# SCH-00005-6.net
KiCad netlist of a schematic drawn in Altium Designer
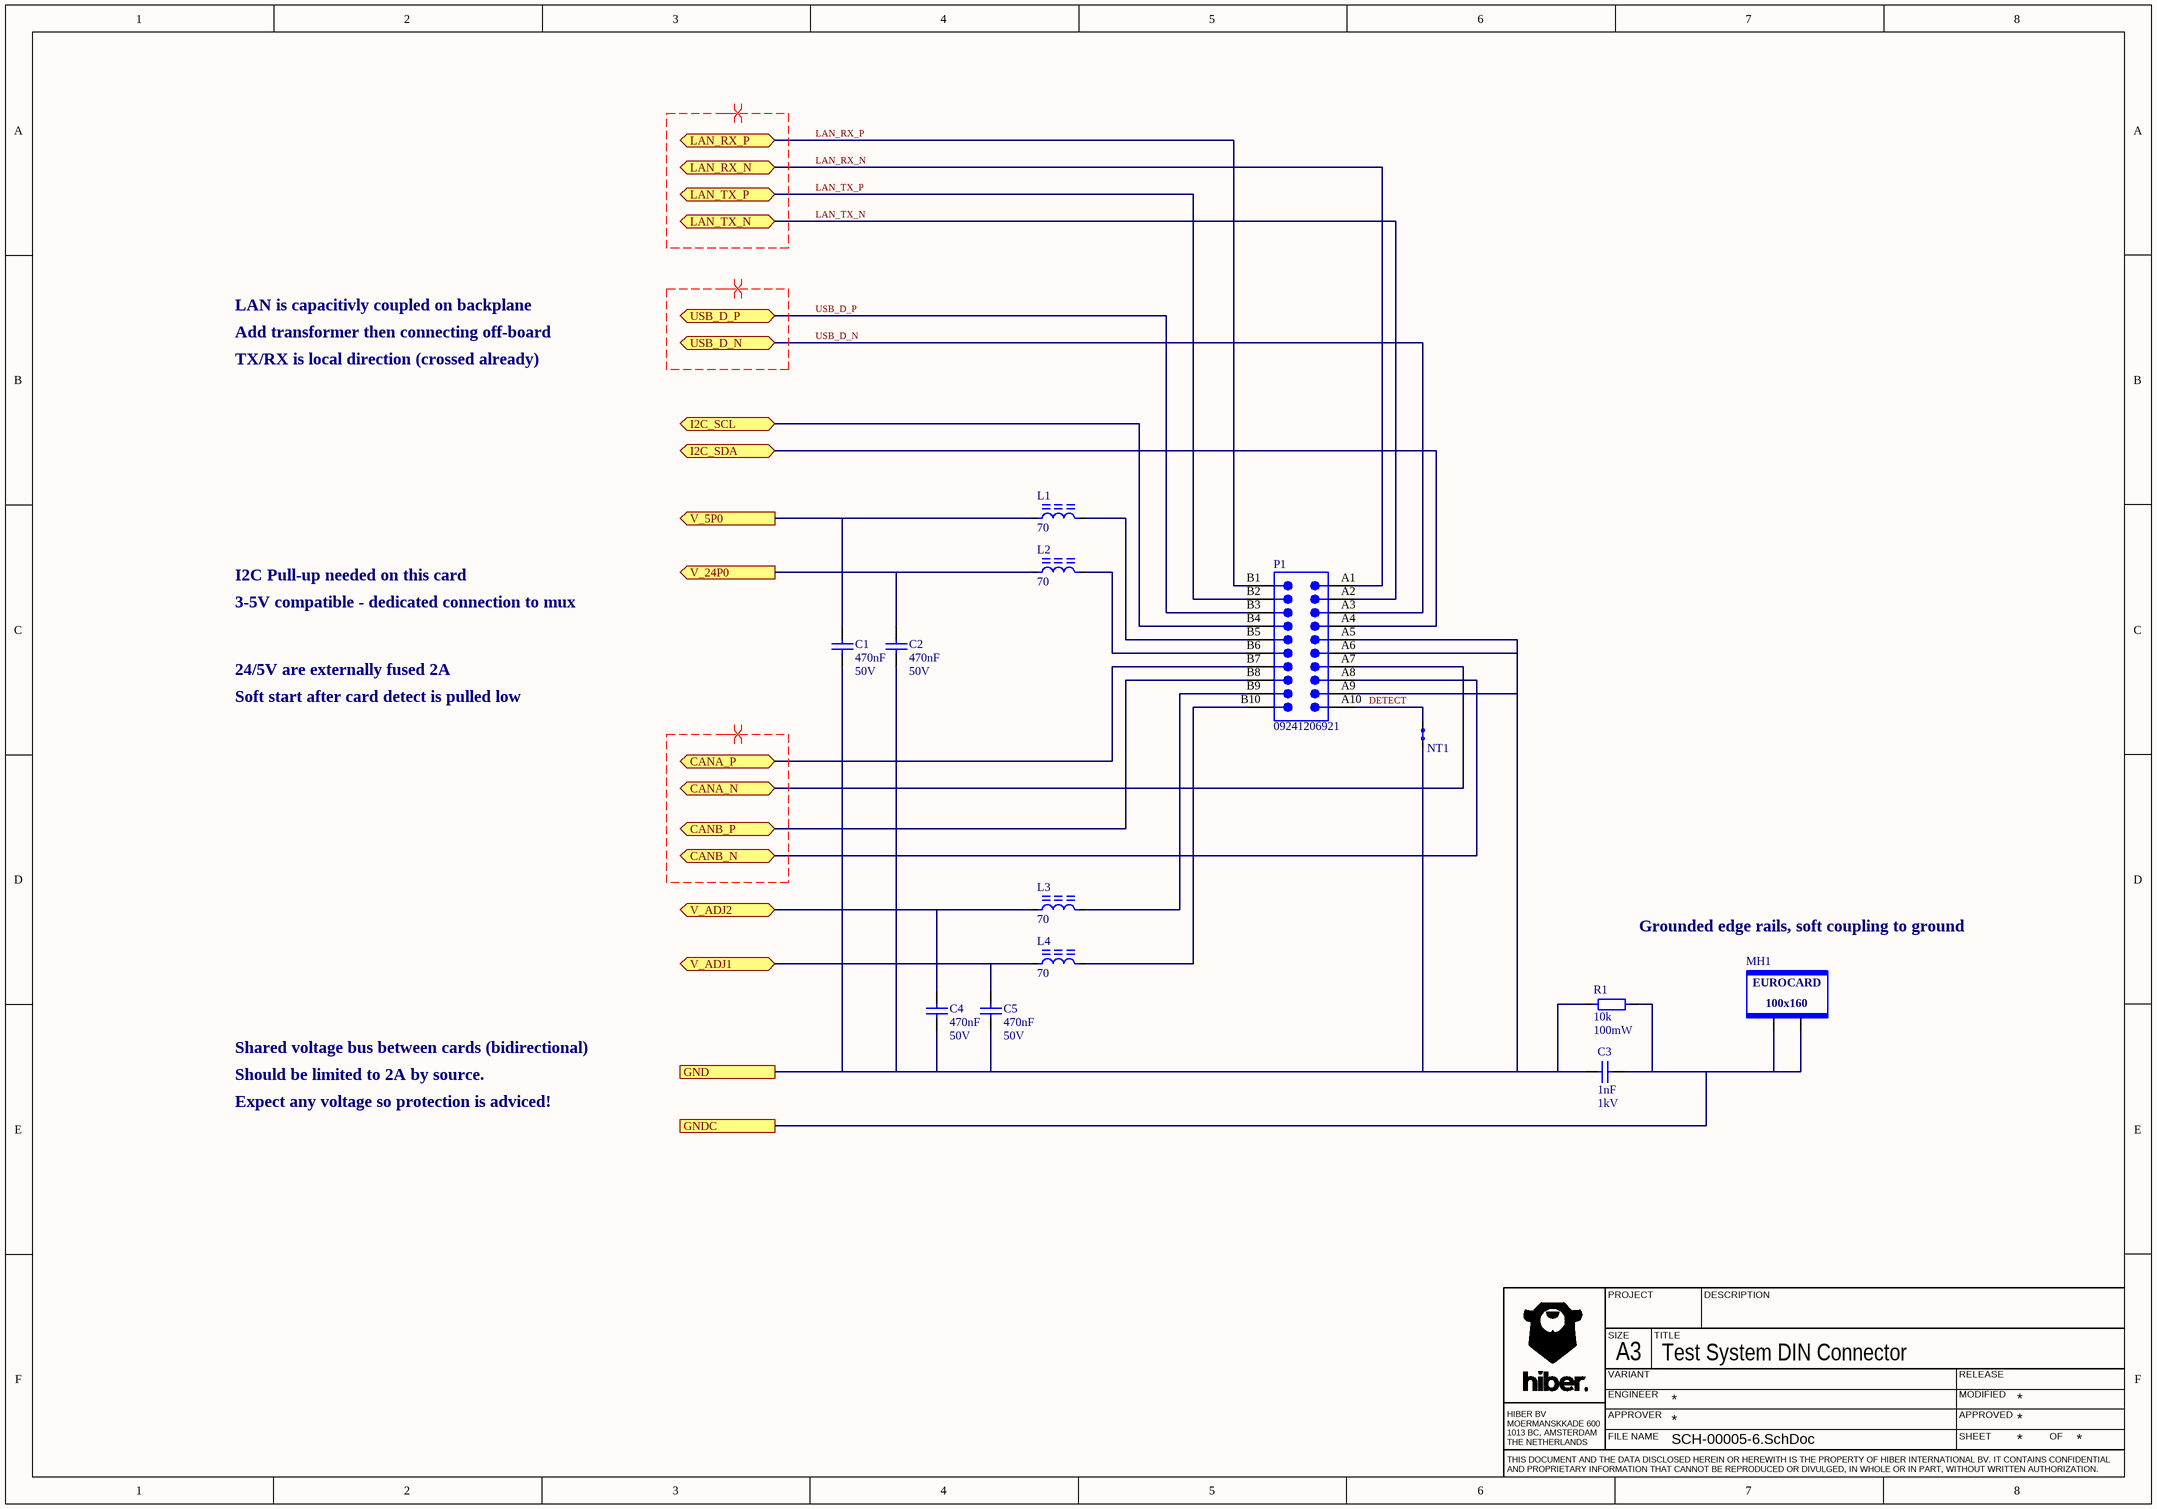
[diagram p0: SCH-00005-6.SchDoc]

(export (version "E")
  (design (tool "Eeschema 10.0.6"))
  (components
    (comp (ref "C1")
      (value "470nF")
      (footprint "CAPC200X125X110L50N")
      (description "CAP Standard 0805 (2012) 470,0nF 50V X7R (Standard)")
      (fields
        (field (name "RATED VOLTAGE") "50V")
        (field (name "TOLERANCE") "10%")
        (field (name "Comment") "C0805C474K5RACTU")
      )
      (libsource (lib "Hiber") (part "CAPACITOR"))
    )
    (comp (ref "C2")
      (value "470nF")
      (footprint "CAPC200X125X110L50N")
      (description "CAP Standard 0805 (2012) 470,0nF 50V X7R (Standard)")
      (fields
        (field (name "RATED VOLTAGE") "50V")
        (field (name "TOLERANCE") "10%")
        (field (name "Comment") "C0805C474K5RACTU")
      )
      (libsource (lib "Hiber") (part "CAPACITOR"))
    )
    (comp (ref "C3")
      (value "1nF")
      (footprint "CAPC160X80X87L35N")
      (description "CAP Automotive 0603 (1608) 1,0nF 1kV X7R (ArcShield with Flexible Termination)")
      (fields
        (field (name "TOLERANCE") "10%")
        (field (name "RATED VOLTAGE") "1kV")
        (field (name "Comment") "C0603W102KDRACAUTO")
      )
      (libsource (lib "Hiber Vault") (part "CAPACITOR"))
    )
    (comp (ref "C4")
      (value "470nF")
      (footprint "CAPC200X125X110L50N")
      (description "CAP Standard 0805 (2012) 470,0nF 50V X7R (Standard)")
      (fields
        (field (name "RATED VOLTAGE") "50V")
        (field (name "TOLERANCE") "10%")
        (field (name "Comment") "C0805C474K5RACTU")
      )
      (libsource (lib "Hiber") (part "CAPACITOR"))
    )
    (comp (ref "C5")
      (value "470nF")
      (footprint "CAPC200X125X110L50N")
      (description "CAP Standard 0805 (2012) 470,0nF 50V X7R (Standard)")
      (fields
        (field (name "RATED VOLTAGE") "50V")
        (field (name "TOLERANCE") "10%")
        (field (name "Comment") "C0805C474K5RACTU")
      )
      (libsource (lib "Hiber") (part "CAPACITOR"))
    )
    (comp (ref "L1")
      (value "BLM21SP700SH1D")
      (footprint "BEADC200X125X105L50N")
      (description "IND, Automotive, Chip Ferrite Bead, Power Lines, 0805, 70R, 6A")
      (fields (field (name "IMPEDANCE") "70") (field (name "TOLERANCE") "25%"))
      (libsource (lib "Hiber") (part "INDUCTOR-FERRITE"))
    )
    (comp (ref "L2")
      (value "BLM21SP700SH1D")
      (footprint "BEADC200X125X105L50N")
      (description "IND, Automotive, Chip Ferrite Bead, Power Lines, 0805, 70R, 6A")
      (fields (field (name "IMPEDANCE") "70") (field (name "TOLERANCE") "25%"))
      (libsource (lib "Hiber") (part "INDUCTOR-FERRITE"))
    )
    (comp (ref "L3")
      (value "BLM21SP700SH1D")
      (footprint "BEADC200X125X105L50N")
      (description "IND, Automotive, Chip Ferrite Bead, Power Lines, 0805, 70R, 6A")
      (fields (field (name "IMPEDANCE") "70") (field (name "TOLERANCE") "25%"))
      (libsource (lib "Hiber") (part "INDUCTOR-FERRITE"))
    )
    (comp (ref "L4")
      (value "BLM21SP700SH1D")
      (footprint "BEADC200X125X105L50N")
      (description "IND, Automotive, Chip Ferrite Bead, Power Lines, 0805, 70R, 6A")
      (fields (field (name "IMPEDANCE") "70") (field (name "TOLERANCE") "25%"))
      (libsource (lib "Hiber") (part "INDUCTOR-FERRITE"))
    )
    (comp (ref "MH1")
      (value "EUROCARD_160X100")
      (footprint "EUROCARD_100X160")
      (description "Eurocard board outline 100x160mm")
      (libsource (lib "Hiber") (part "EUROCARD"))
    )
    (comp (ref "NT1")
      (value "NET-TIE")
      (footprint "NT200")
      (description "Net Tie, Inline")
      (libsource (lib "Hiber") (part "NET-TIE"))
    )
    (comp (ref "P1")
      (value "09241206921")
      (footprint "HARTING_09241206921")
      (description "Headers and Edge Type Connector")
      (libsource (lib "Hiber") (part "DIN41612-3B-MALE"))
    )
    (comp (ref "R1")
      (value "10k")
      (footprint "RESC160X85X55L30N")
      (description "RES High Stability Thin Film 0603 10K0 ±0.1% 0,1W")
      (fields
        (field (name "RATED POWER") "100mW")
        (field (name "TOLERANCE") "0.1%")
        (field (name "Comment") "TNPW060310K0BEEA")
      )
      (libsource (lib "Hiber Vault") (part "RESISTOR-2P"))
    )
  )
  (nets
    (net (code "1") (name "/CANA_N") (class "Default")
      (node (ref "P1") (pin "A7") (pinfunction "A7_A7") (pintype "passive"))
    )
    (net (code "2") (name "/CANA_P") (class "Default")
      (node (ref "P1") (pin "B7") (pinfunction "B7_B7") (pintype "passive"))
    )
    (net (code "3") (name "/CANB_N") (class "Default")
      (node (ref "P1") (pin "A8") (pinfunction "A8_A8") (pintype "passive"))
    )
    (net (code "4") (name "/CANB_P") (class "Default")
      (node (ref "P1") (pin "B8") (pinfunction "B8_B8") (pintype "passive"))
    )
    (net (code "5") (name "/DETECT") (class "Default")
      (node (ref "NT1") (pin "2") (pinfunction "1_2") (pintype "passive"))
      (node (ref "P1") (pin "A10") (pinfunction "A10_A10") (pintype "passive"))
    )
    (net (code "6") (name "/GND") (class "Default")
      (node (ref "C1") (pin "1") (pinfunction "1_1") (pintype "passive"))
      (node (ref "C2") (pin "1") (pinfunction "1_1") (pintype "passive"))
      (node (ref "C3") (pin "2") (pinfunction "2_2") (pintype "passive"))
      (node (ref "C4") (pin "1") (pinfunction "1_1") (pintype "passive"))
      (node (ref "C5") (pin "1") (pinfunction "1_1") (pintype "passive"))
      (node (ref "NT1") (pin "1") (pinfunction "1_1") (pintype "passive"))
      (node (ref "P1") (pin "A5") (pinfunction "A5_A5") (pintype "passive"))
      (node (ref "P1") (pin "A6") (pinfunction "A6_A6") (pintype "passive"))
      (node (ref "P1") (pin "A9") (pinfunction "A9_A9") (pintype "passive"))
      (node (ref "R1") (pin "1") (pinfunction "1_1") (pintype "passive"))
    )
    (net (code "7") (name "/GNDC") (class "Default")
      (node (ref "C3") (pin "1") (pinfunction "1_1") (pintype "passive"))
      (node (ref "MH1") (pin "1") (pinfunction "1_1") (pintype "passive"))
      (node (ref "MH1") (pin "2") (pinfunction "2_2") (pintype "passive"))
      (node (ref "R1") (pin "2") (pinfunction "2_2") (pintype "passive"))
    )
    (net (code "8") (name "/I2C_SCL") (class "Default")
      (node (ref "P1") (pin "B4") (pinfunction "B4_B4") (pintype "passive"))
    )
    (net (code "9") (name "/I2C_SDA") (class "Default")
      (node (ref "P1") (pin "A4") (pinfunction "A4_A4") (pintype "passive"))
    )
    (net (code "10") (name "/LAN_RX_N") (class "Default")
      (node (ref "P1") (pin "A1") (pinfunction "A1_A1") (pintype "passive"))
    )
    (net (code "11") (name "/LAN_RX_P") (class "Default")
      (node (ref "P1") (pin "B1") (pinfunction "B1_B1") (pintype "passive"))
    )
    (net (code "12") (name "/LAN_TX_N") (class "Default")
      (node (ref "P1") (pin "A2") (pinfunction "A2_A2") (pintype "passive"))
    )
    (net (code "13") (name "/LAN_TX_P") (class "Default")
      (node (ref "P1") (pin "B2") (pinfunction "B2_B2") (pintype "passive"))
    )
    (net (code "14") (name "/USB_D_N") (class "Default")
      (node (ref "P1") (pin "A3") (pinfunction "A3_A3") (pintype "passive"))
    )
    (net (code "15") (name "/USB_D_P") (class "Default")
      (node (ref "P1") (pin "B3") (pinfunction "B3_B3") (pintype "passive"))
    )
    (net (code "16") (name "/V_5P0") (class "Default")
      (node (ref "C1") (pin "2") (pinfunction "2_2") (pintype "passive"))
      (node (ref "L1") (pin "1") (pinfunction "1_1") (pintype "passive"))
    )
    (net (code "17") (name "/V_24P0") (class "Default")
      (node (ref "C2") (pin "2") (pinfunction "2_2") (pintype "passive"))
      (node (ref "L2") (pin "1") (pinfunction "1_1") (pintype "passive"))
    )
    (net (code "18") (name "/V_ADJ1") (class "Default")
      (node (ref "C5") (pin "2") (pinfunction "2_2") (pintype "passive"))
      (node (ref "L4") (pin "1") (pinfunction "1_1") (pintype "passive"))
    )
    (net (code "19") (name "/V_ADJ2") (class "Default")
      (node (ref "C4") (pin "2") (pinfunction "2_2") (pintype "passive"))
      (node (ref "L3") (pin "1") (pinfunction "1_1") (pintype "passive"))
    )
    (net (code "20") (name "Net-(L1-Pad2)") (class "Default")
      (node (ref "L1") (pin "2") (pinfunction "2_2") (pintype "passive"))
      (node (ref "P1") (pin "B5") (pinfunction "B5_B5") (pintype "passive"))
    )
    (net (code "21") (name "Net-(L2-Pad2)") (class "Default")
      (node (ref "L2") (pin "2") (pinfunction "2_2") (pintype "passive"))
      (node (ref "P1") (pin "B6") (pinfunction "B6_B6") (pintype "passive"))
    )
    (net (code "22") (name "Net-(L3-Pad2)") (class "Default")
      (node (ref "L3") (pin "2") (pinfunction "2_2") (pintype "passive"))
      (node (ref "P1") (pin "B9") (pinfunction "B9_B9") (pintype "passive"))
    )
    (net (code "23") (name "Net-(L4-Pad2)") (class "Default")
      (node (ref "L4") (pin "2") (pinfunction "2_2") (pintype "passive"))
      (node (ref "P1") (pin "B10") (pinfunction "B10_B10") (pintype "passive"))
    )
  )
)
